# con-bot-j2-0.net
KiCad netlist of a schematic drawn in Altium Designer
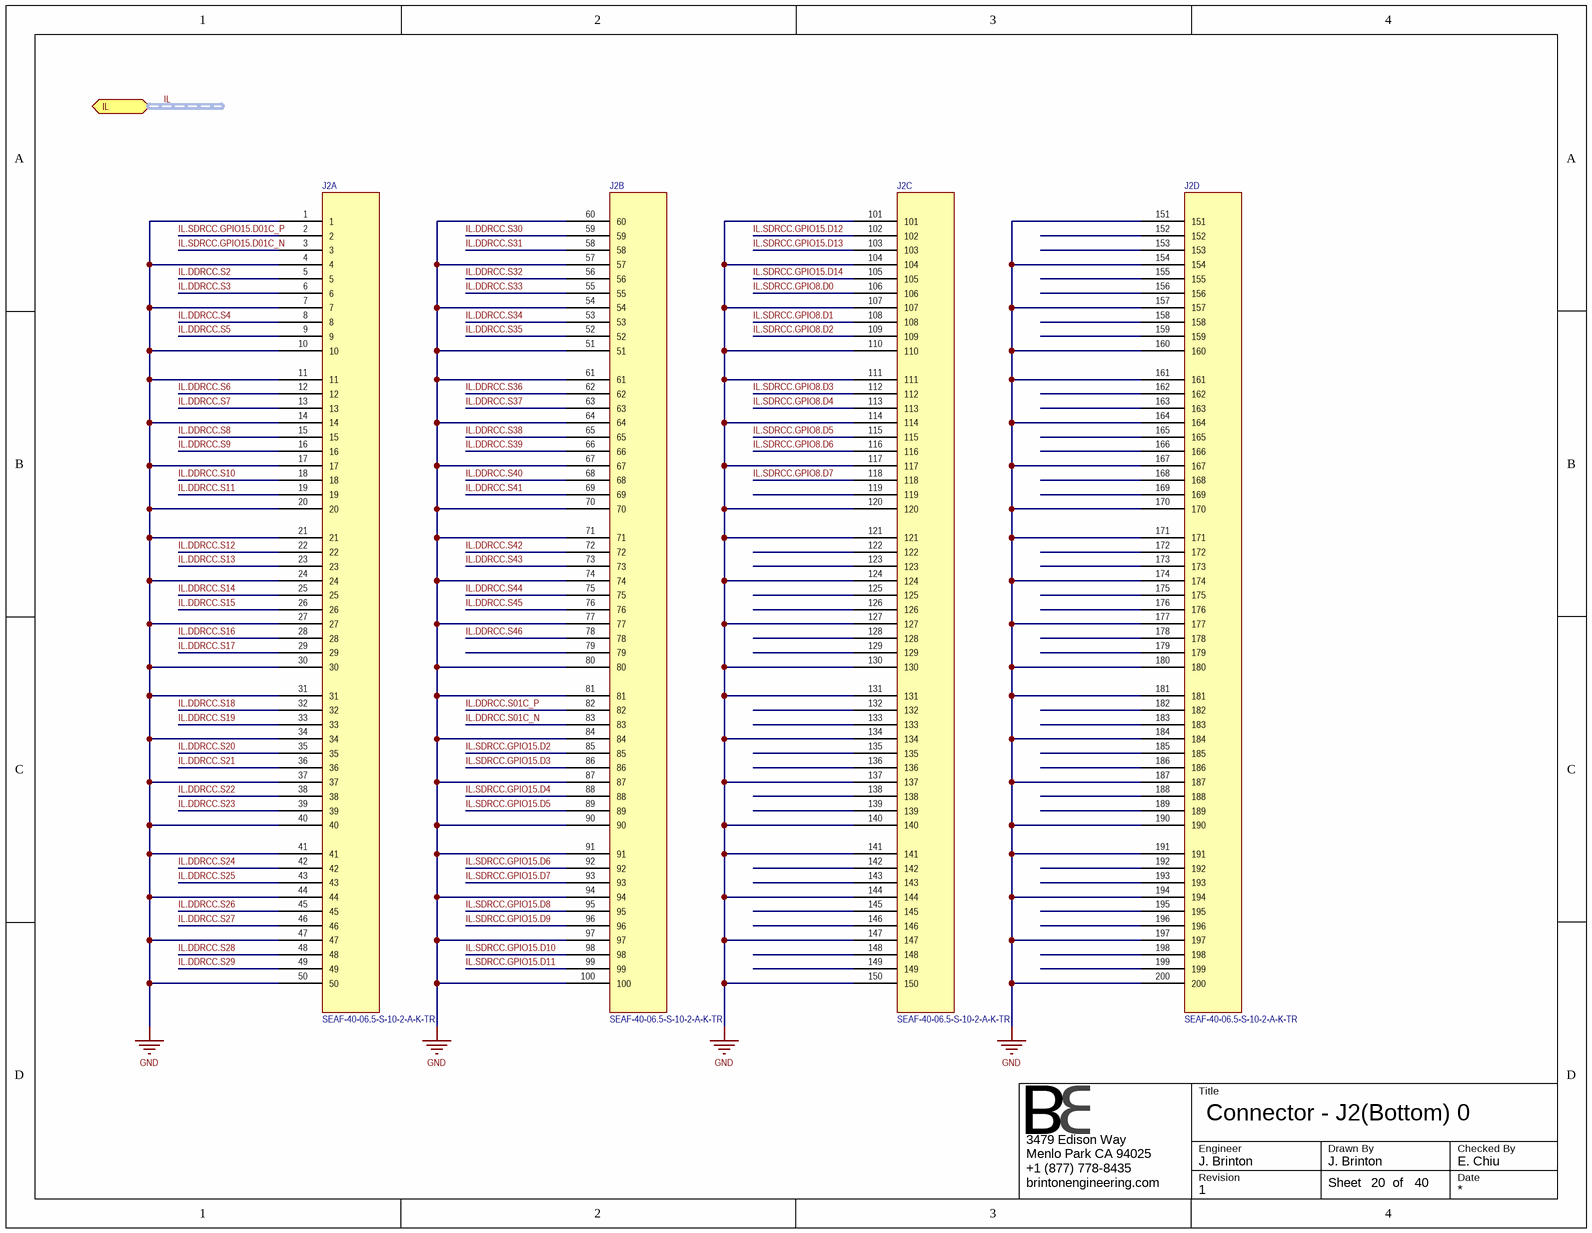
[diagram p0: con-bot-j2-0.SchDoc]

(export (version "E")
  (design (tool "Eeschema 10.0.6"))
  (components
    (comp (ref "J2")
      (value "SEAF-40-06.5-S-10-2-A-K-TR")
      (footprint "samtec:SEAF-40-06.5-S-10-2-A-K-TR")
      (description "Terminal Array Assembly, Surface Mount, 0.050\" Pitch, 400 Pins")
      (fields (field (name "MANUFACTURER") "Samtec"))
      (libsource (lib "samtec") (part "SEAF-40-06.5-S-10-2-A-K-TR"))
    )
  )
  (nets
    (net (code "2") (name "/IL.DDRCC.S01C_N") (class "Default")
      (node (ref "J2") (pin "83") (pinfunction "83_83") (pintype "passive"))
    )
    (net (code "3") (name "/IL.DDRCC.S01C_P") (class "Default")
      (node (ref "J2") (pin "82") (pinfunction "82_82") (pintype "passive"))
    )
    (net (code "4") (name "/IL.DDRCC.S2") (class "Default")
      (node (ref "J2") (pin "5") (pinfunction "5_5") (pintype "passive"))
    )
    (net (code "5") (name "/IL.DDRCC.S3") (class "Default")
      (node (ref "J2") (pin "6") (pinfunction "6_6") (pintype "passive"))
    )
    (net (code "6") (name "/IL.DDRCC.S4") (class "Default")
      (node (ref "J2") (pin "8") (pinfunction "8_8") (pintype "passive"))
    )
    (net (code "7") (name "/IL.DDRCC.S5") (class "Default")
      (node (ref "J2") (pin "9") (pinfunction "9_9") (pintype "passive"))
    )
    (net (code "8") (name "/IL.DDRCC.S6") (class "Default")
      (node (ref "J2") (pin "12") (pinfunction "12_12") (pintype "passive"))
    )
    (net (code "9") (name "/IL.DDRCC.S7") (class "Default")
      (node (ref "J2") (pin "13") (pinfunction "13_13") (pintype "passive"))
    )
    (net (code "10") (name "/IL.DDRCC.S8") (class "Default")
      (node (ref "J2") (pin "15") (pinfunction "15_15") (pintype "passive"))
    )
    (net (code "11") (name "/IL.DDRCC.S9") (class "Default")
      (node (ref "J2") (pin "16") (pinfunction "16_16") (pintype "passive"))
    )
    (net (code "12") (name "/IL.DDRCC.S10") (class "Default")
      (node (ref "J2") (pin "18") (pinfunction "18_18") (pintype "passive"))
    )
    (net (code "13") (name "/IL.DDRCC.S11") (class "Default")
      (node (ref "J2") (pin "19") (pinfunction "19_19") (pintype "passive"))
    )
    (net (code "14") (name "/IL.DDRCC.S12") (class "Default")
      (node (ref "J2") (pin "22") (pinfunction "22_22") (pintype "passive"))
    )
    (net (code "15") (name "/IL.DDRCC.S13") (class "Default")
      (node (ref "J2") (pin "23") (pinfunction "23_23") (pintype "passive"))
    )
    (net (code "16") (name "/IL.DDRCC.S14") (class "Default")
      (node (ref "J2") (pin "25") (pinfunction "25_25") (pintype "passive"))
    )
    (net (code "17") (name "/IL.DDRCC.S15") (class "Default")
      (node (ref "J2") (pin "26") (pinfunction "26_26") (pintype "passive"))
    )
    (net (code "18") (name "/IL.DDRCC.S16") (class "Default")
      (node (ref "J2") (pin "28") (pinfunction "28_28") (pintype "passive"))
    )
    (net (code "19") (name "/IL.DDRCC.S17") (class "Default")
      (node (ref "J2") (pin "29") (pinfunction "29_29") (pintype "passive"))
    )
    (net (code "20") (name "/IL.DDRCC.S18") (class "Default")
      (node (ref "J2") (pin "32") (pinfunction "32_32") (pintype "passive"))
    )
    (net (code "21") (name "/IL.DDRCC.S19") (class "Default")
      (node (ref "J2") (pin "33") (pinfunction "33_33") (pintype "passive"))
    )
    (net (code "22") (name "/IL.DDRCC.S20") (class "Default")
      (node (ref "J2") (pin "35") (pinfunction "35_35") (pintype "passive"))
    )
    (net (code "23") (name "/IL.DDRCC.S21") (class "Default")
      (node (ref "J2") (pin "36") (pinfunction "36_36") (pintype "passive"))
    )
    (net (code "24") (name "/IL.DDRCC.S22") (class "Default")
      (node (ref "J2") (pin "38") (pinfunction "38_38") (pintype "passive"))
    )
    (net (code "25") (name "/IL.DDRCC.S23") (class "Default")
      (node (ref "J2") (pin "39") (pinfunction "39_39") (pintype "passive"))
    )
    (net (code "26") (name "/IL.DDRCC.S24") (class "Default")
      (node (ref "J2") (pin "42") (pinfunction "42_42") (pintype "passive"))
    )
    (net (code "27") (name "/IL.DDRCC.S25") (class "Default")
      (node (ref "J2") (pin "43") (pinfunction "43_43") (pintype "passive"))
    )
    (net (code "28") (name "/IL.DDRCC.S26") (class "Default")
      (node (ref "J2") (pin "45") (pinfunction "45_45") (pintype "passive"))
    )
    (net (code "29") (name "/IL.DDRCC.S27") (class "Default")
      (node (ref "J2") (pin "46") (pinfunction "46_46") (pintype "passive"))
    )
    (net (code "30") (name "/IL.DDRCC.S28") (class "Default")
      (node (ref "J2") (pin "48") (pinfunction "48_48") (pintype "passive"))
    )
    (net (code "31") (name "/IL.DDRCC.S29") (class "Default")
      (node (ref "J2") (pin "49") (pinfunction "49_49") (pintype "passive"))
    )
    (net (code "32") (name "/IL.DDRCC.S30") (class "Default")
      (node (ref "J2") (pin "59") (pinfunction "59_59") (pintype "passive"))
    )
    (net (code "33") (name "/IL.DDRCC.S31") (class "Default")
      (node (ref "J2") (pin "58") (pinfunction "58_58") (pintype "passive"))
    )
    (net (code "34") (name "/IL.DDRCC.S32") (class "Default")
      (node (ref "J2") (pin "56") (pinfunction "56_56") (pintype "passive"))
    )
    (net (code "35") (name "/IL.DDRCC.S33") (class "Default")
      (node (ref "J2") (pin "55") (pinfunction "55_55") (pintype "passive"))
    )
    (net (code "36") (name "/IL.DDRCC.S34") (class "Default")
      (node (ref "J2") (pin "53") (pinfunction "53_53") (pintype "passive"))
    )
    (net (code "37") (name "/IL.DDRCC.S35") (class "Default")
      (node (ref "J2") (pin "52") (pinfunction "52_52") (pintype "passive"))
    )
    (net (code "38") (name "/IL.DDRCC.S36") (class "Default")
      (node (ref "J2") (pin "62") (pinfunction "62_62") (pintype "passive"))
    )
    (net (code "39") (name "/IL.DDRCC.S37") (class "Default")
      (node (ref "J2") (pin "63") (pinfunction "63_63") (pintype "passive"))
    )
    (net (code "40") (name "/IL.DDRCC.S38") (class "Default")
      (node (ref "J2") (pin "65") (pinfunction "65_65") (pintype "passive"))
    )
    (net (code "41") (name "/IL.DDRCC.S39") (class "Default")
      (node (ref "J2") (pin "66") (pinfunction "66_66") (pintype "passive"))
    )
    (net (code "42") (name "/IL.DDRCC.S40") (class "Default")
      (node (ref "J2") (pin "68") (pinfunction "68_68") (pintype "passive"))
    )
    (net (code "43") (name "/IL.DDRCC.S41") (class "Default")
      (node (ref "J2") (pin "69") (pinfunction "69_69") (pintype "passive"))
    )
    (net (code "44") (name "/IL.DDRCC.S42") (class "Default")
      (node (ref "J2") (pin "72") (pinfunction "72_72") (pintype "passive"))
    )
    (net (code "45") (name "/IL.DDRCC.S43") (class "Default")
      (node (ref "J2") (pin "73") (pinfunction "73_73") (pintype "passive"))
    )
    (net (code "46") (name "/IL.DDRCC.S44") (class "Default")
      (node (ref "J2") (pin "75") (pinfunction "75_75") (pintype "passive"))
    )
    (net (code "47") (name "/IL.DDRCC.S45") (class "Default")
      (node (ref "J2") (pin "76") (pinfunction "76_76") (pintype "passive"))
    )
    (net (code "48") (name "/IL.DDRCC.S46") (class "Default")
      (node (ref "J2") (pin "78") (pinfunction "78_78") (pintype "passive"))
    )
    (net (code "49") (name "/IL.SDRCC.GPIO8.D0") (class "Default")
      (node (ref "J2") (pin "106") (pinfunction "106_106") (pintype "passive"))
    )
    (net (code "50") (name "/IL.SDRCC.GPIO8.D1") (class "Default")
      (node (ref "J2") (pin "108") (pinfunction "108_108") (pintype "passive"))
    )
    (net (code "51") (name "/IL.SDRCC.GPIO8.D2") (class "Default")
      (node (ref "J2") (pin "109") (pinfunction "109_109") (pintype "passive"))
    )
    (net (code "52") (name "/IL.SDRCC.GPIO8.D3") (class "Default")
      (node (ref "J2") (pin "112") (pinfunction "112_112") (pintype "passive"))
    )
    (net (code "53") (name "/IL.SDRCC.GPIO8.D4") (class "Default")
      (node (ref "J2") (pin "113") (pinfunction "113_113") (pintype "passive"))
    )
    (net (code "54") (name "/IL.SDRCC.GPIO8.D5") (class "Default")
      (node (ref "J2") (pin "115") (pinfunction "115_115") (pintype "passive"))
    )
    (net (code "55") (name "/IL.SDRCC.GPIO8.D6") (class "Default")
      (node (ref "J2") (pin "116") (pinfunction "116_116") (pintype "passive"))
    )
    (net (code "56") (name "/IL.SDRCC.GPIO8.D7") (class "Default")
      (node (ref "J2") (pin "118") (pinfunction "118_118") (pintype "passive"))
    )
    (net (code "57") (name "/IL.SDRCC.GPIO15.D01C_N") (class "Default")
      (node (ref "J2") (pin "3") (pinfunction "3_3") (pintype "passive"))
    )
    (net (code "58") (name "/IL.SDRCC.GPIO15.D01C_P") (class "Default")
      (node (ref "J2") (pin "2") (pinfunction "2_2") (pintype "passive"))
    )
    (net (code "59") (name "/IL.SDRCC.GPIO15.D2") (class "Default")
      (node (ref "J2") (pin "85") (pinfunction "85_85") (pintype "passive"))
    )
    (net (code "60") (name "/IL.SDRCC.GPIO15.D3") (class "Default")
      (node (ref "J2") (pin "86") (pinfunction "86_86") (pintype "passive"))
    )
    (net (code "61") (name "/IL.SDRCC.GPIO15.D4") (class "Default")
      (node (ref "J2") (pin "88") (pinfunction "88_88") (pintype "passive"))
    )
    (net (code "62") (name "/IL.SDRCC.GPIO15.D5") (class "Default")
      (node (ref "J2") (pin "89") (pinfunction "89_89") (pintype "passive"))
    )
    (net (code "63") (name "/IL.SDRCC.GPIO15.D6") (class "Default")
      (node (ref "J2") (pin "92") (pinfunction "92_92") (pintype "passive"))
    )
    (net (code "64") (name "/IL.SDRCC.GPIO15.D7") (class "Default")
      (node (ref "J2") (pin "93") (pinfunction "93_93") (pintype "passive"))
    )
    (net (code "65") (name "/IL.SDRCC.GPIO15.D8") (class "Default")
      (node (ref "J2") (pin "95") (pinfunction "95_95") (pintype "passive"))
    )
    (net (code "66") (name "/IL.SDRCC.GPIO15.D9") (class "Default")
      (node (ref "J2") (pin "96") (pinfunction "96_96") (pintype "passive"))
    )
    (net (code "67") (name "/IL.SDRCC.GPIO15.D10") (class "Default")
      (node (ref "J2") (pin "98") (pinfunction "98_98") (pintype "passive"))
    )
    (net (code "68") (name "/IL.SDRCC.GPIO15.D11") (class "Default")
      (node (ref "J2") (pin "99") (pinfunction "99_99") (pintype "passive"))
    )
    (net (code "69") (name "/IL.SDRCC.GPIO15.D12") (class "Default")
      (node (ref "J2") (pin "102") (pinfunction "102_102") (pintype "passive"))
    )
    (net (code "70") (name "/IL.SDRCC.GPIO15.D13") (class "Default")
      (node (ref "J2") (pin "103") (pinfunction "103_103") (pintype "passive"))
    )
    (net (code "71") (name "/IL.SDRCC.GPIO15.D14") (class "Default")
      (node (ref "J2") (pin "105") (pinfunction "105_105") (pintype "passive"))
    )
    (net (code "73") (name "GND") (class "Default")
      (node (ref "J2") (pin "1") (pinfunction "1_1") (pintype "passive"))
      (node (ref "J2") (pin "10") (pinfunction "10_10") (pintype "passive"))
      (node (ref "J2") (pin "100") (pinfunction "100_100") (pintype "passive"))
      (node (ref "J2") (pin "101") (pinfunction "101_101") (pintype "passive"))
      (node (ref "J2") (pin "104") (pinfunction "104_104") (pintype "passive"))
      (node (ref "J2") (pin "107") (pinfunction "107_107") (pintype "passive"))
      (node (ref "J2") (pin "11") (pinfunction "11_11") (pintype "passive"))
      (node (ref "J2") (pin "110") (pinfunction "110_110") (pintype "passive"))
      (node (ref "J2") (pin "111") (pinfunction "111_111") (pintype "passive"))
      (node (ref "J2") (pin "114") (pinfunction "114_114") (pintype "passive"))
      (node (ref "J2") (pin "117") (pinfunction "117_117") (pintype "passive"))
      (node (ref "J2") (pin "120") (pinfunction "120_120") (pintype "passive"))
      (node (ref "J2") (pin "121") (pinfunction "121_121") (pintype "passive"))
      (node (ref "J2") (pin "124") (pinfunction "124_124") (pintype "passive"))
      (node (ref "J2") (pin "127") (pinfunction "127_127") (pintype "passive"))
      (node (ref "J2") (pin "130") (pinfunction "130_130") (pintype "passive"))
      (node (ref "J2") (pin "131") (pinfunction "131_131") (pintype "passive"))
      (node (ref "J2") (pin "134") (pinfunction "134_134") (pintype "passive"))
      (node (ref "J2") (pin "137") (pinfunction "137_137") (pintype "passive"))
      (node (ref "J2") (pin "14") (pinfunction "14_14") (pintype "passive"))
      (node (ref "J2") (pin "140") (pinfunction "140_140") (pintype "passive"))
      (node (ref "J2") (pin "141") (pinfunction "141_141") (pintype "passive"))
      (node (ref "J2") (pin "144") (pinfunction "144_144") (pintype "passive"))
      (node (ref "J2") (pin "147") (pinfunction "147_147") (pintype "passive"))
      (node (ref "J2") (pin "150") (pinfunction "150_150") (pintype "passive"))
      (node (ref "J2") (pin "151") (pinfunction "151_151") (pintype "passive"))
      (node (ref "J2") (pin "154") (pinfunction "154_154") (pintype "passive"))
      (node (ref "J2") (pin "157") (pinfunction "157_157") (pintype "passive"))
      (node (ref "J2") (pin "160") (pinfunction "160_160") (pintype "passive"))
      (node (ref "J2") (pin "161") (pinfunction "161_161") (pintype "passive"))
      (node (ref "J2") (pin "164") (pinfunction "164_164") (pintype "passive"))
      (node (ref "J2") (pin "167") (pinfunction "167_167") (pintype "passive"))
      (node (ref "J2") (pin "17") (pinfunction "17_17") (pintype "passive"))
      (node (ref "J2") (pin "170") (pinfunction "170_170") (pintype "passive"))
      (node (ref "J2") (pin "171") (pinfunction "171_171") (pintype "passive"))
      (node (ref "J2") (pin "174") (pinfunction "174_174") (pintype "passive"))
      (node (ref "J2") (pin "177") (pinfunction "177_177") (pintype "passive"))
      (node (ref "J2") (pin "180") (pinfunction "180_180") (pintype "passive"))
      (node (ref "J2") (pin "181") (pinfunction "181_181") (pintype "passive"))
      (node (ref "J2") (pin "184") (pinfunction "184_184") (pintype "passive"))
      (node (ref "J2") (pin "187") (pinfunction "187_187") (pintype "passive"))
      (node (ref "J2") (pin "190") (pinfunction "190_190") (pintype "passive"))
      (node (ref "J2") (pin "191") (pinfunction "191_191") (pintype "passive"))
      (node (ref "J2") (pin "194") (pinfunction "194_194") (pintype "passive"))
      (node (ref "J2") (pin "197") (pinfunction "197_197") (pintype "passive"))
      (node (ref "J2") (pin "20") (pinfunction "20_20") (pintype "passive"))
      (node (ref "J2") (pin "200") (pinfunction "200_200") (pintype "passive"))
      (node (ref "J2") (pin "21") (pinfunction "21_21") (pintype "passive"))
      (node (ref "J2") (pin "24") (pinfunction "24_24") (pintype "passive"))
      (node (ref "J2") (pin "27") (pinfunction "27_27") (pintype "passive"))
      (node (ref "J2") (pin "30") (pinfunction "30_30") (pintype "passive"))
      (node (ref "J2") (pin "31") (pinfunction "31_31") (pintype "passive"))
      (node (ref "J2") (pin "34") (pinfunction "34_34") (pintype "passive"))
      (node (ref "J2") (pin "37") (pinfunction "37_37") (pintype "passive"))
      (node (ref "J2") (pin "4") (pinfunction "4_4") (pintype "passive"))
      (node (ref "J2") (pin "40") (pinfunction "40_40") (pintype "passive"))
      (node (ref "J2") (pin "41") (pinfunction "41_41") (pintype "passive"))
      (node (ref "J2") (pin "44") (pinfunction "44_44") (pintype "passive"))
      (node (ref "J2") (pin "47") (pinfunction "47_47") (pintype "passive"))
      (node (ref "J2") (pin "50") (pinfunction "50_50") (pintype "passive"))
      (node (ref "J2") (pin "51") (pinfunction "51_51") (pintype "passive"))
      (node (ref "J2") (pin "54") (pinfunction "54_54") (pintype "passive"))
      (node (ref "J2") (pin "57") (pinfunction "57_57") (pintype "passive"))
      (node (ref "J2") (pin "60") (pinfunction "60_60") (pintype "passive"))
      (node (ref "J2") (pin "61") (pinfunction "61_61") (pintype "passive"))
      (node (ref "J2") (pin "64") (pinfunction "64_64") (pintype "passive"))
      (node (ref "J2") (pin "67") (pinfunction "67_67") (pintype "passive"))
      (node (ref "J2") (pin "7") (pinfunction "7_7") (pintype "passive"))
      (node (ref "J2") (pin "70") (pinfunction "70_70") (pintype "passive"))
      (node (ref "J2") (pin "71") (pinfunction "71_71") (pintype "passive"))
      (node (ref "J2") (pin "74") (pinfunction "74_74") (pintype "passive"))
      (node (ref "J2") (pin "77") (pinfunction "77_77") (pintype "passive"))
      (node (ref "J2") (pin "80") (pinfunction "80_80") (pintype "passive"))
      (node (ref "J2") (pin "81") (pinfunction "81_81") (pintype "passive"))
      (node (ref "J2") (pin "84") (pinfunction "84_84") (pintype "passive"))
      (node (ref "J2") (pin "87") (pinfunction "87_87") (pintype "passive"))
      (node (ref "J2") (pin "90") (pinfunction "90_90") (pintype "passive"))
      (node (ref "J2") (pin "91") (pinfunction "91_91") (pintype "passive"))
      (node (ref "J2") (pin "94") (pinfunction "94_94") (pintype "passive"))
      (node (ref "J2") (pin "97") (pinfunction "97_97") (pintype "passive"))
    )
    (net (code "74") (name "unconnected-(J2-Pad79)") (class "Default")
      (node (ref "J2") (pin "79") (pinfunction "79_79") (pintype "passive"))
    )
    (net (code "75") (name "unconnected-(J2-Pad119)") (class "Default")
      (node (ref "J2") (pin "119") (pinfunction "119_119") (pintype "passive"))
    )
    (net (code "76") (name "unconnected-(J2-Pad122)") (class "Default")
      (node (ref "J2") (pin "122") (pinfunction "122_122") (pintype "passive"))
    )
    (net (code "77") (name "unconnected-(J2-Pad123)") (class "Default")
      (node (ref "J2") (pin "123") (pinfunction "123_123") (pintype "passive"))
    )
    (net (code "78") (name "unconnected-(J2-Pad125)") (class "Default")
      (node (ref "J2") (pin "125") (pinfunction "125_125") (pintype "passive"))
    )
    (net (code "79") (name "unconnected-(J2-Pad126)") (class "Default")
      (node (ref "J2") (pin "126") (pinfunction "126_126") (pintype "passive"))
    )
    (net (code "80") (name "unconnected-(J2-Pad128)") (class "Default")
      (node (ref "J2") (pin "128") (pinfunction "128_128") (pintype "passive"))
    )
    (net (code "81") (name "unconnected-(J2-Pad129)") (class "Default")
      (node (ref "J2") (pin "129") (pinfunction "129_129") (pintype "passive"))
    )
    (net (code "82") (name "unconnected-(J2-Pad132)") (class "Default")
      (node (ref "J2") (pin "132") (pinfunction "132_132") (pintype "passive"))
    )
    (net (code "83") (name "unconnected-(J2-Pad133)") (class "Default")
      (node (ref "J2") (pin "133") (pinfunction "133_133") (pintype "passive"))
    )
    (net (code "84") (name "unconnected-(J2-Pad135)") (class "Default")
      (node (ref "J2") (pin "135") (pinfunction "135_135") (pintype "passive"))
    )
    (net (code "85") (name "unconnected-(J2-Pad136)") (class "Default")
      (node (ref "J2") (pin "136") (pinfunction "136_136") (pintype "passive"))
    )
    (net (code "86") (name "unconnected-(J2-Pad138)") (class "Default")
      (node (ref "J2") (pin "138") (pinfunction "138_138") (pintype "passive"))
    )
    (net (code "87") (name "unconnected-(J2-Pad139)") (class "Default")
      (node (ref "J2") (pin "139") (pinfunction "139_139") (pintype "passive"))
    )
    (net (code "88") (name "unconnected-(J2-Pad142)") (class "Default")
      (node (ref "J2") (pin "142") (pinfunction "142_142") (pintype "passive"))
    )
    (net (code "89") (name "unconnected-(J2-Pad143)") (class "Default")
      (node (ref "J2") (pin "143") (pinfunction "143_143") (pintype "passive"))
    )
    (net (code "90") (name "unconnected-(J2-Pad145)") (class "Default")
      (node (ref "J2") (pin "145") (pinfunction "145_145") (pintype "passive"))
    )
    (net (code "91") (name "unconnected-(J2-Pad146)") (class "Default")
      (node (ref "J2") (pin "146") (pinfunction "146_146") (pintype "passive"))
    )
    (net (code "92") (name "unconnected-(J2-Pad148)") (class "Default")
      (node (ref "J2") (pin "148") (pinfunction "148_148") (pintype "passive"))
    )
    (net (code "93") (name "unconnected-(J2-Pad149)") (class "Default")
      (node (ref "J2") (pin "149") (pinfunction "149_149") (pintype "passive"))
    )
    (net (code "94") (name "unconnected-(J2-Pad152)") (class "Default")
      (node (ref "J2") (pin "152") (pinfunction "152_152") (pintype "passive"))
    )
    (net (code "95") (name "unconnected-(J2-Pad153)") (class "Default")
      (node (ref "J2") (pin "153") (pinfunction "153_153") (pintype "passive"))
    )
    (net (code "96") (name "unconnected-(J2-Pad155)") (class "Default")
      (node (ref "J2") (pin "155") (pinfunction "155_155") (pintype "passive"))
    )
    (net (code "97") (name "unconnected-(J2-Pad156)") (class "Default")
      (node (ref "J2") (pin "156") (pinfunction "156_156") (pintype "passive"))
    )
    (net (code "98") (name "unconnected-(J2-Pad158)") (class "Default")
      (node (ref "J2") (pin "158") (pinfunction "158_158") (pintype "passive"))
    )
    (net (code "99") (name "unconnected-(J2-Pad159)") (class "Default")
      (node (ref "J2") (pin "159") (pinfunction "159_159") (pintype "passive"))
    )
    (net (code "100") (name "unconnected-(J2-Pad162)") (class "Default")
      (node (ref "J2") (pin "162") (pinfunction "162_162") (pintype "passive"))
    )
    (net (code "101") (name "unconnected-(J2-Pad163)") (class "Default")
      (node (ref "J2") (pin "163") (pinfunction "163_163") (pintype "passive"))
    )
    (net (code "102") (name "unconnected-(J2-Pad165)") (class "Default")
      (node (ref "J2") (pin "165") (pinfunction "165_165") (pintype "passive"))
    )
    (net (code "103") (name "unconnected-(J2-Pad166)") (class "Default")
      (node (ref "J2") (pin "166") (pinfunction "166_166") (pintype "passive"))
    )
    (net (code "104") (name "unconnected-(J2-Pad168)") (class "Default")
      (node (ref "J2") (pin "168") (pinfunction "168_168") (pintype "passive"))
    )
    (net (code "105") (name "unconnected-(J2-Pad169)") (class "Default")
      (node (ref "J2") (pin "169") (pinfunction "169_169") (pintype "passive"))
    )
    (net (code "106") (name "unconnected-(J2-Pad172)") (class "Default")
      (node (ref "J2") (pin "172") (pinfunction "172_172") (pintype "passive"))
    )
    (net (code "107") (name "unconnected-(J2-Pad173)") (class "Default")
      (node (ref "J2") (pin "173") (pinfunction "173_173") (pintype "passive"))
    )
    (net (code "108") (name "unconnected-(J2-Pad175)") (class "Default")
      (node (ref "J2") (pin "175") (pinfunction "175_175") (pintype "passive"))
    )
    (net (code "109") (name "unconnected-(J2-Pad176)") (class "Default")
      (node (ref "J2") (pin "176") (pinfunction "176_176") (pintype "passive"))
    )
    (net (code "110") (name "unconnected-(J2-Pad178)") (class "Default")
      (node (ref "J2") (pin "178") (pinfunction "178_178") (pintype "passive"))
    )
    (net (code "111") (name "unconnected-(J2-Pad179)") (class "Default")
      (node (ref "J2") (pin "179") (pinfunction "179_179") (pintype "passive"))
    )
    (net (code "112") (name "unconnected-(J2-Pad182)") (class "Default")
      (node (ref "J2") (pin "182") (pinfunction "182_182") (pintype "passive"))
    )
    (net (code "113") (name "unconnected-(J2-Pad183)") (class "Default")
      (node (ref "J2") (pin "183") (pinfunction "183_183") (pintype "passive"))
    )
    (net (code "114") (name "unconnected-(J2-Pad185)") (class "Default")
      (node (ref "J2") (pin "185") (pinfunction "185_185") (pintype "passive"))
    )
    (net (code "115") (name "unconnected-(J2-Pad186)") (class "Default")
      (node (ref "J2") (pin "186") (pinfunction "186_186") (pintype "passive"))
    )
    (net (code "116") (name "unconnected-(J2-Pad188)") (class "Default")
      (node (ref "J2") (pin "188") (pinfunction "188_188") (pintype "passive"))
    )
    (net (code "117") (name "unconnected-(J2-Pad189)") (class "Default")
      (node (ref "J2") (pin "189") (pinfunction "189_189") (pintype "passive"))
    )
    (net (code "118") (name "unconnected-(J2-Pad192)") (class "Default")
      (node (ref "J2") (pin "192") (pinfunction "192_192") (pintype "passive"))
    )
    (net (code "119") (name "unconnected-(J2-Pad193)") (class "Default")
      (node (ref "J2") (pin "193") (pinfunction "193_193") (pintype "passive"))
    )
    (net (code "120") (name "unconnected-(J2-Pad195)") (class "Default")
      (node (ref "J2") (pin "195") (pinfunction "195_195") (pintype "passive"))
    )
    (net (code "121") (name "unconnected-(J2-Pad196)") (class "Default")
      (node (ref "J2") (pin "196") (pinfunction "196_196") (pintype "passive"))
    )
    (net (code "122") (name "unconnected-(J2-Pad198)") (class "Default")
      (node (ref "J2") (pin "198") (pinfunction "198_198") (pintype "passive"))
    )
    (net (code "123") (name "unconnected-(J2-Pad199)") (class "Default")
      (node (ref "J2") (pin "199") (pinfunction "199_199") (pintype "passive"))
    )
  )
)
